# MPU6050.net
KiCad netlist of a schematic drawn in Altium Designer
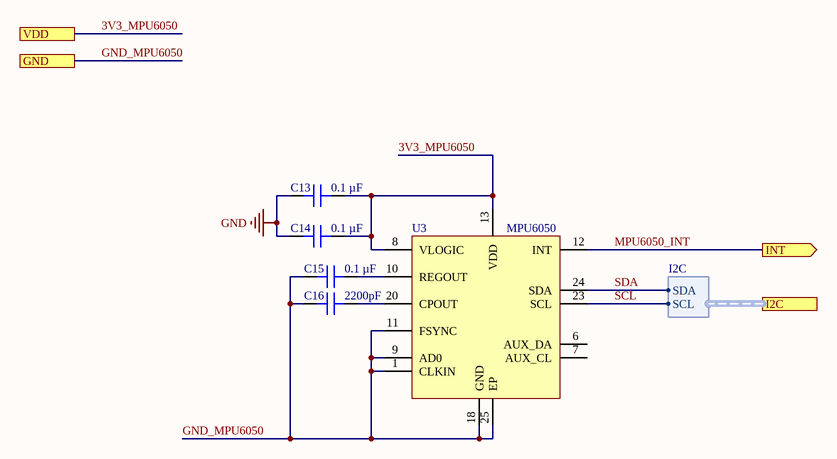
[diagram p0: MPU6050.SchDoc]

(export (version "E")
  (design (tool "Eeschema 10.0.6"))
  (components
    (comp (ref "C13")
      (value "0.1 µF")
      (footprint "CAP 0402_1005")
      (description "CAP CER 0.1UF 16V X7R 0402")
      (fields (field (name "PART NUMBER") "C0402C104K4RACAUTO") (field (name "MANUFACTURER") "KEMET"))
      (libsource (lib "Celestial Altium Library - altium_library") (part "Capacitor"))
    )
    (comp (ref "C14")
      (value "0.1 µF")
      (footprint "CAP 0402_1005")
      (description "CAP CER 0.1UF 16V X7R 0402")
      (fields (field (name "PART NUMBER") "C0402C104K4RACAUTO") (field (name "MANUFACTURER") "KEMET"))
      (libsource (lib "Celestial Altium Library - altium_library") (part "Capacitor"))
    )
    (comp (ref "C15")
      (value "0.1 µF")
      (footprint "CAP 0402_1005")
      (description "CAP CER 0.1UF 16V X7R 0402")
      (fields (field (name "PART NUMBER") "C0402C104K4RACAUTO") (field (name "MANUFACTURER") "KEMET"))
      (libsource (lib "Celestial Altium Library - altium_library") (part "Capacitor"))
    )
    (comp (ref "C16")
      (value "2200pF")
      (footprint "CAP 0603_1608")
      (description "CAP CER 2200PF 50V 0603 EPOXY")
      (fields
        (field (name "PART NUMBER") "CGA3E2X8R1H222M080AD")
        (field (name "MANUFACTURER") "TDK Corporation")
      )
      (libsource (lib "Celestial Altium Library - altium_library") (part "Capacitor"))
    )
    (comp (ref "U3") (value "MPU6050") (footprint "IC_MPU6050") (libsource (lib "IC") (part "MPU6050")))
  )
  (nets
    (net (code "2") (name "/3V3_MPU6050") (class "Default")
      (node (ref "C13") (pin "1") (pinfunction "1_1") (pintype "passive"))
      (node (ref "C14") (pin "1") (pinfunction "1_1") (pintype "passive"))
      (node (ref "U3") (pin "13") (pinfunction "VDD_13") (pintype "passive"))
      (node (ref "U3") (pin "8") (pinfunction "VLOGIC_8") (pintype "passive"))
    )
    (net (code "3") (name "/MPU6050_INT") (class "Default")
      (node (ref "U3") (pin "12") (pinfunction "INT_12") (pintype "passive"))
    )
    (net (code "4") (name "/SCL") (class "Default")
      (node (ref "U3") (pin "23") (pinfunction "SCL_23") (pintype "passive"))
    )
    (net (code "5") (name "/SDA") (class "Default")
      (node (ref "U3") (pin "24") (pinfunction "SDA_24") (pintype "passive"))
    )
    (net (code "7") (name "GND") (class "Default")
      (node (ref "C13") (pin "2") (pinfunction "2_2") (pintype "passive"))
      (node (ref "C14") (pin "2") (pinfunction "2_2") (pintype "passive"))
      (node (ref "C15") (pin "2") (pinfunction "2_2") (pintype "passive"))
      (node (ref "C16") (pin "2") (pinfunction "2_2") (pintype "passive"))
      (node (ref "U3") (pin "1") (pinfunction "CLKIN_1") (pintype "passive"))
      (node (ref "U3") (pin "11") (pinfunction "FSYNC_11") (pintype "passive"))
      (node (ref "U3") (pin "18") (pinfunction "GND_18") (pintype "passive"))
      (node (ref "U3") (pin "25") (pinfunction "EP_25") (pintype "passive"))
      (node (ref "U3") (pin "9") (pinfunction "AD0_9") (pintype "passive"))
    )
    (net (code "8") (name "Net-(U3-CPOUT)") (class "Default")
      (node (ref "C16") (pin "1") (pinfunction "1_1") (pintype "passive"))
      (node (ref "U3") (pin "20") (pinfunction "CPOUT_20") (pintype "passive"))
    )
    (net (code "9") (name "Net-(U3-REGOUT)") (class "Default")
      (node (ref "C15") (pin "1") (pinfunction "1_1") (pintype "passive"))
      (node (ref "U3") (pin "10") (pinfunction "REGOUT_10") (pintype "passive"))
    )
    (net (code "10") (name "unconnected-(U3-AUX_CL-Pad7)") (class "Default")
      (node (ref "U3") (pin "7") (pinfunction "AUX_CL_7") (pintype "passive"))
    )
    (net (code "11") (name "unconnected-(U3-AUX_DA-Pad6)") (class "Default")
      (node (ref "U3") (pin "6") (pinfunction "AUX_DA_6") (pintype "passive"))
    )
  )
)
